# arduino_helper.net
KiCad netlist of a schematic drawn in EAGLE
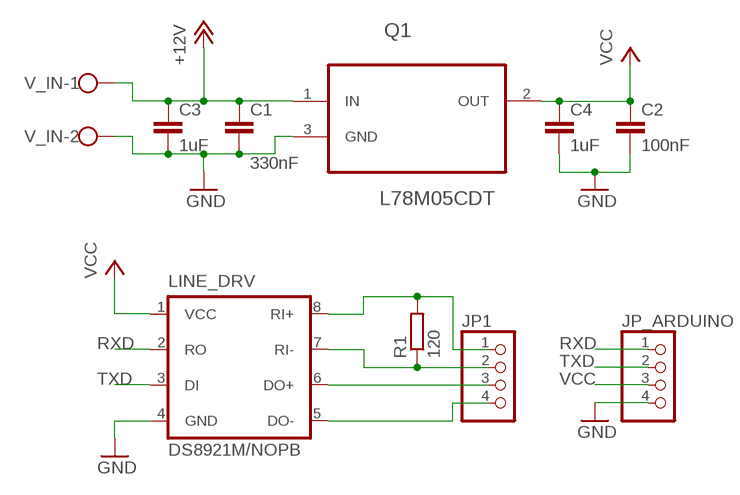
[diagram p0: schematic, sheet 1]

(export (version "E")
  (design (tool "Eeschema 10.0.6"))
  (components
    (comp (ref "C1")
      (value "330nF")
      (footprint "eagle-import:C0805")
      (libsource (lib "eagle-import") (part "C-EUC0805"))
    )
    (comp (ref "C2")
      (value "100nF")
      (footprint "eagle-import:C0805")
      (libsource (lib "eagle-import") (part "C-EUC0805"))
    )
    (comp (ref "C3")
      (value "1uF")
      (footprint "eagle-import:C0805")
      (libsource (lib "eagle-import") (part "C-EUC0805"))
    )
    (comp (ref "C4")
      (value "1uF")
      (footprint "eagle-import:C0805")
      (libsource (lib "eagle-import") (part "C-EUC0805"))
    )
    (comp (ref "JP1")
      (value "PINHD-1X4")
      (footprint "eagle-import:1X04")
      (libsource (lib "eagle-import") (part "PINHD-1X4"))
    )
    (comp (ref "JP_ARDUINO")
      (value "PINHD-1X4")
      (footprint "eagle-import:1X04")
      (libsource (lib "eagle-import") (part "PINHD-1X4"))
    )
    (comp (ref "LINE_DRV")
      (value "DS8921M/NOPB")
      (footprint "eagle-import:SOIC8")
      (libsource (lib "eagle-import") (part "DS8921M/NOPB"))
    )
    (comp (ref "Q1")
      (value "L78M05CDT")
      (footprint "eagle-import:TO225P972X240-3N")
      (libsource (lib "eagle-import") (part "L78M05CDT"))
    )
    (comp (ref "R1")
      (value "120")
      (footprint "eagle-import:R0805")
      (libsource (lib "eagle-import") (part "R-EU_R0805"))
    )
    (comp (ref "V_IN")
      (value "W237-102")
      (footprint "eagle-import:W237-102")
      (fields (field (name "MPN") "237-102"))
      (libsource (lib "eagle-import") (part "W237-102"))
    )
  )
  (nets
    (net (code "1") (name "+12V") (class "Default")
      (node (ref "C1") (pin "1") (pinfunction "1_1") (pintype "passive"))
      (node (ref "C3") (pin "1") (pinfunction "1_1") (pintype "passive"))
      (node (ref "Q1") (pin "1") (pinfunction "IN_1") (pintype "input"))
      (node (ref "V_IN") (pin "1") (pinfunction "KL_1") (pintype "passive"))
    )
    (net (code "2") (name "/RXD") (class "Default")
      (node (ref "JP_ARDUINO") (pin "1") (pinfunction "1_1") (pintype "passive"))
      (node (ref "LINE_DRV") (pin "2") (pinfunction "RO_2") (pintype "output"))
    )
    (net (code "3") (name "/TXD") (class "Default")
      (node (ref "JP_ARDUINO") (pin "2") (pinfunction "2_2") (pintype "passive"))
      (node (ref "LINE_DRV") (pin "3") (pinfunction "DI_3") (pintype "input"))
    )
    (net (code "4") (name "GND") (class "Default")
      (node (ref "C1") (pin "2") (pinfunction "2_2") (pintype "passive"))
      (node (ref "C2") (pin "2") (pinfunction "2_2") (pintype "passive"))
      (node (ref "C3") (pin "2") (pinfunction "2_2") (pintype "passive"))
      (node (ref "C4") (pin "2") (pinfunction "2_2") (pintype "passive"))
      (node (ref "JP_ARDUINO") (pin "4") (pinfunction "4_4") (pintype "passive"))
      (node (ref "LINE_DRV") (pin "4") (pinfunction "GND_4") (pintype "power_in"))
      (node (ref "Q1") (pin "3") (pinfunction "GND_3") (pintype "passive"))
      (node (ref "V_IN") (pin "2") (pinfunction "KL_2") (pintype "passive"))
    )
    (net (code "5") (name "Net-(LINE_DRV-DO+)") (class "Default")
      (node (ref "JP1") (pin "3") (pinfunction "3_3") (pintype "passive"))
      (node (ref "LINE_DRV") (pin "6") (pinfunction "DO+_6") (pintype "output"))
    )
    (net (code "6") (name "Net-(LINE_DRV-DO-)") (class "Default")
      (node (ref "JP1") (pin "4") (pinfunction "4_4") (pintype "passive"))
      (node (ref "LINE_DRV") (pin "5") (pinfunction "DO-_5") (pintype "output"))
    )
    (net (code "7") (name "Net-(LINE_DRV-RI+)") (class "Default")
      (node (ref "JP1") (pin "1") (pinfunction "1_1") (pintype "passive"))
      (node (ref "LINE_DRV") (pin "8") (pinfunction "RI+_8") (pintype "input"))
      (node (ref "R1") (pin "2") (pinfunction "2_2") (pintype "passive"))
    )
    (net (code "8") (name "Net-(LINE_DRV-RI-)") (class "Default")
      (node (ref "JP1") (pin "2") (pinfunction "2_2") (pintype "passive"))
      (node (ref "LINE_DRV") (pin "7") (pinfunction "RI-_7") (pintype "input"))
      (node (ref "R1") (pin "1") (pinfunction "1_1") (pintype "passive"))
    )
    (net (code "9") (name "VCC") (class "Default")
      (node (ref "C2") (pin "1") (pinfunction "1_1") (pintype "passive"))
      (node (ref "C4") (pin "1") (pinfunction "1_1") (pintype "passive"))
      (node (ref "JP_ARDUINO") (pin "3") (pinfunction "3_3") (pintype "passive"))
      (node (ref "LINE_DRV") (pin "1") (pinfunction "VCC_1") (pintype "power_in"))
      (node (ref "Q1") (pin "2") (pinfunction "OUT_2") (pintype "output"))
    )
  )
)
